# LED_Bar_Board.net
KiCad netlist of a schematic drawn in EAGLE
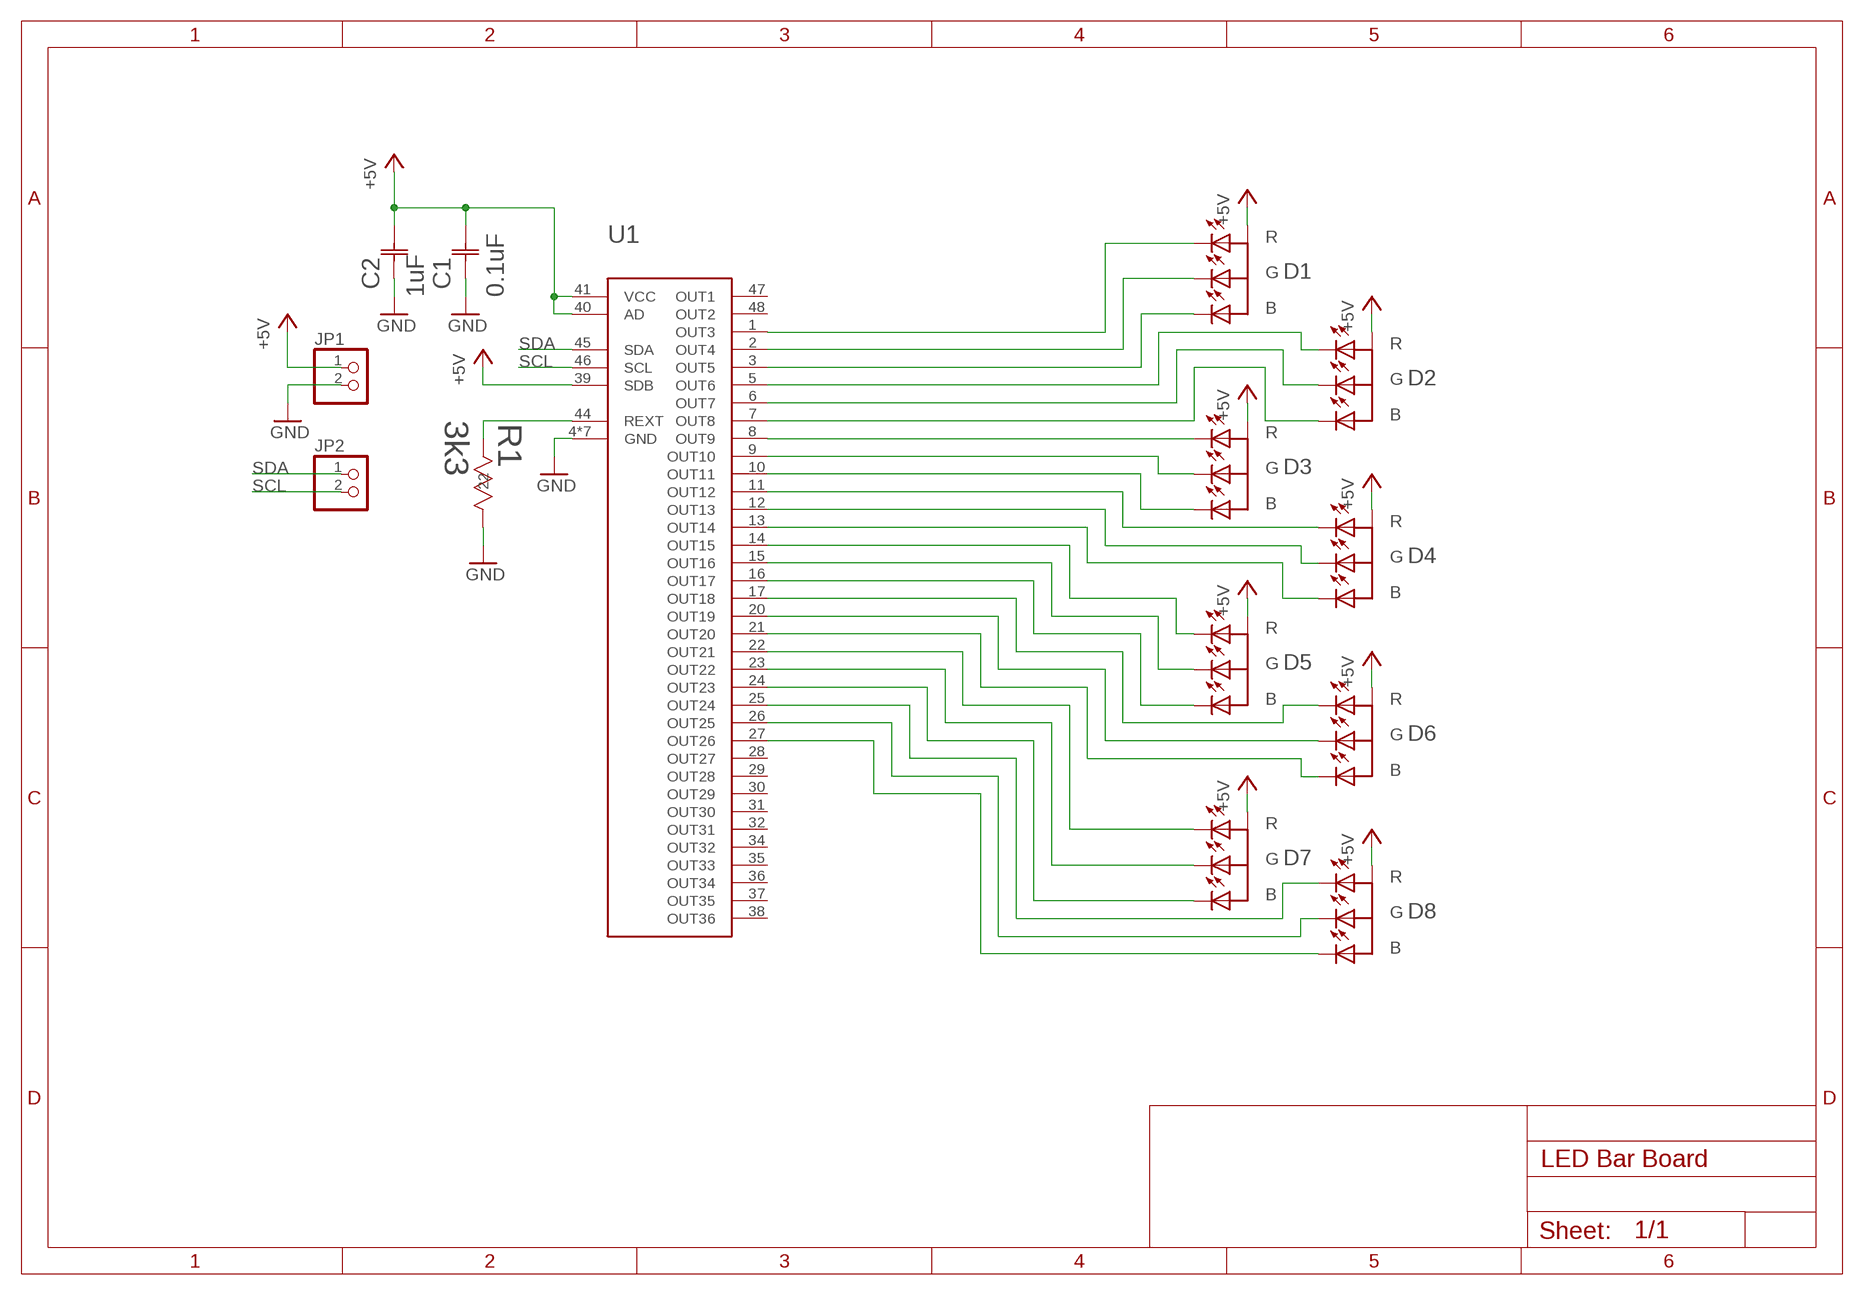
[diagram p0: schematic, sheet 1]

(export (version "E")
  (design (tool "Eeschema 10.0.6"))
  (components
    (comp (ref "C1")
      (value "0.1uF")
      (footprint "eagle-import:0805")
      (fields
        (field (name "MANUFACTURER_PART_NUMBER") "08055C104KAT2A")
        (field (name "COPYRIGHT") "Copyright C 2015 Accelerated Designs. All rights reserved")
      )
      (libsource (lib "eagle-import") (part "08055C104KAT2A"))
    )
    (comp (ref "C2")
      (value "1uF")
      (footprint "eagle-import:YAG_CC0805")
      (fields
        (field (name "MANUFACTURER_PART_NUMBER") "CC0805KKX7R7BB105")
        (field (name "COPYRIGHT") "Copyright C 2015 Accelerated Designs. All rights reserved")
      )
      (libsource (lib "eagle-import") (part "CC0805KKX7R7BB105"))
    )
    (comp (ref "D1")
      (value "ASMB-MTB0-0A3A2")
      (footprint "eagle-import:ASMB-MTB0_LED")
      (libsource (lib "eagle-import") (part "ASMB-MTB0-0A3A2"))
    )
    (comp (ref "D2")
      (value "ASMB-MTB0-0A3A2")
      (footprint "eagle-import:ASMB-MTB0_LED")
      (libsource (lib "eagle-import") (part "ASMB-MTB0-0A3A2"))
    )
    (comp (ref "D3")
      (value "ASMB-MTB0-0A3A2")
      (footprint "eagle-import:ASMB-MTB0_LED")
      (libsource (lib "eagle-import") (part "ASMB-MTB0-0A3A2"))
    )
    (comp (ref "D4")
      (value "ASMB-MTB0-0A3A2")
      (footprint "eagle-import:ASMB-MTB0_LED")
      (libsource (lib "eagle-import") (part "ASMB-MTB0-0A3A2"))
    )
    (comp (ref "D5")
      (value "ASMB-MTB0-0A3A2")
      (footprint "eagle-import:ASMB-MTB0_LED")
      (libsource (lib "eagle-import") (part "ASMB-MTB0-0A3A2"))
    )
    (comp (ref "D6")
      (value "ASMB-MTB0-0A3A2")
      (footprint "eagle-import:ASMB-MTB0_LED")
      (libsource (lib "eagle-import") (part "ASMB-MTB0-0A3A2"))
    )
    (comp (ref "D7")
      (value "ASMB-MTB0-0A3A2")
      (footprint "eagle-import:ASMB-MTB0_LED")
      (libsource (lib "eagle-import") (part "ASMB-MTB0-0A3A2"))
    )
    (comp (ref "D8")
      (value "ASMB-MTB0-0A3A2")
      (footprint "eagle-import:ASMB-MTB0_LED")
      (libsource (lib "eagle-import") (part "ASMB-MTB0-0A3A2"))
    )
    (comp (ref "JP1")
      (value "PINHD-1X2")
      (footprint "eagle-import:1X02")
      (libsource (lib "eagle-import") (part "PINHD-1X2"))
    )
    (comp (ref "JP2")
      (value "PINHD-1X2")
      (footprint "eagle-import:1X02")
      (libsource (lib "eagle-import") (part "PINHD-1X2"))
    )
    (comp (ref "R1")
      (value "3k3")
      (footprint "eagle-import:RC1206N-M")
      (fields (field (name "MANUFACTURER_PART_NUMBER") "RC1206JR073K3L"))
      (libsource (lib "eagle-import") (part "RC1206JR-073K3LRC1206N-M"))
    )
    (comp (ref "U1")
      (value "IS31FL3236")
      (footprint "eagle-import:TQFP-48")
      (libsource (lib "eagle-import") (part "IS31FL3236"))
    )
  )
  (nets
    (net (code "1") (name "+5V") (class "Default")
      (node (ref "C1") (pin "2") (pinfunction "2_2") (pintype "passive"))
      (node (ref "C2") (pin "2") (pinfunction "22_2") (pintype "passive"))
      (node (ref "D1") (pin "1") (pinfunction "A_1") (pintype "passive"))
      (node (ref "D2") (pin "1") (pinfunction "A_1") (pintype "passive"))
      (node (ref "D3") (pin "1") (pinfunction "A_1") (pintype "passive"))
      (node (ref "D4") (pin "1") (pinfunction "A_1") (pintype "passive"))
      (node (ref "D5") (pin "1") (pinfunction "A_1") (pintype "passive"))
      (node (ref "D6") (pin "1") (pinfunction "A_1") (pintype "passive"))
      (node (ref "D7") (pin "1") (pinfunction "A_1") (pintype "passive"))
      (node (ref "D8") (pin "1") (pinfunction "A_1") (pintype "passive"))
      (node (ref "JP1") (pin "1") (pinfunction "1_1") (pintype "passive"))
      (node (ref "U1") (pin "39") (pinfunction "SDB_39") (pintype "bidirectional"))
      (node (ref "U1") (pin "40") (pinfunction "AD_40") (pintype "bidirectional"))
      (node (ref "U1") (pin "41") (pinfunction "VCC_41") (pintype "bidirectional"))
    )
    (net (code "2") (name "/SCL") (class "Default")
      (node (ref "JP2") (pin "2") (pinfunction "2_2") (pintype "passive"))
      (node (ref "U1") (pin "46") (pinfunction "SCL_46") (pintype "bidirectional"))
    )
    (net (code "3") (name "/SDA") (class "Default")
      (node (ref "JP2") (pin "1") (pinfunction "1_1") (pintype "passive"))
      (node (ref "U1") (pin "45") (pinfunction "SDA_45") (pintype "bidirectional"))
    )
    (net (code "4") (name "GND") (class "Default")
      (node (ref "C1") (pin "1") (pinfunction "1_1") (pintype "passive"))
      (node (ref "C2") (pin "1") (pinfunction "11_1") (pintype "passive"))
      (node (ref "JP1") (pin "2") (pinfunction "2_2") (pintype "passive"))
      (node (ref "R1") (pin "1") (pinfunction "11_1") (pintype "passive"))
      (node (ref "U1") (pin "18") (pinfunction "GND_18") (pintype "bidirectional"))
      (node (ref "U1") (pin "19") (pinfunction "GND_19") (pintype "bidirectional"))
      (node (ref "U1") (pin "33") (pinfunction "GND_33") (pintype "bidirectional"))
      (node (ref "U1") (pin "4") (pinfunction "GND_4") (pintype "bidirectional"))
      (node (ref "U1") (pin "42") (pinfunction "GND_42") (pintype "bidirectional"))
      (node (ref "U1") (pin "43") (pinfunction "GND_43") (pintype "bidirectional"))
      (node (ref "U1") (pin "EP") (pinfunction "GND_EP") (pintype "bidirectional"))
    )
    (net (code "5") (name "Net-(D1-B)") (class "Default")
      (node (ref "D1") (pin "2") (pinfunction "B_2") (pintype "passive"))
      (node (ref "U1") (pin "3") (pinfunction "OUT5_3") (pintype "bidirectional"))
    )
    (net (code "6") (name "Net-(D1-G)") (class "Default")
      (node (ref "D1") (pin "3") (pinfunction "G_3") (pintype "passive"))
      (node (ref "U1") (pin "2") (pinfunction "OUT4_2") (pintype "bidirectional"))
    )
    (net (code "7") (name "Net-(D1-R)") (class "Default")
      (node (ref "D1") (pin "4") (pinfunction "R_4") (pintype "passive"))
      (node (ref "U1") (pin "1") (pinfunction "OUT3_1") (pintype "bidirectional"))
    )
    (net (code "8") (name "Net-(D2-B)") (class "Default")
      (node (ref "D2") (pin "2") (pinfunction "B_2") (pintype "passive"))
      (node (ref "U1") (pin "7") (pinfunction "OUT8_7") (pintype "bidirectional"))
    )
    (net (code "9") (name "Net-(D2-G)") (class "Default")
      (node (ref "D2") (pin "3") (pinfunction "G_3") (pintype "passive"))
      (node (ref "U1") (pin "6") (pinfunction "OUT7_6") (pintype "bidirectional"))
    )
    (net (code "10") (name "Net-(D2-R)") (class "Default")
      (node (ref "D2") (pin "4") (pinfunction "R_4") (pintype "passive"))
      (node (ref "U1") (pin "5") (pinfunction "OUT6_5") (pintype "bidirectional"))
    )
    (net (code "11") (name "Net-(D3-B)") (class "Default")
      (node (ref "D3") (pin "2") (pinfunction "B_2") (pintype "passive"))
      (node (ref "U1") (pin "10") (pinfunction "OUT11_10") (pintype "bidirectional"))
    )
    (net (code "12") (name "Net-(D3-G)") (class "Default")
      (node (ref "D3") (pin "3") (pinfunction "G_3") (pintype "passive"))
      (node (ref "U1") (pin "9") (pinfunction "OUT10_9") (pintype "bidirectional"))
    )
    (net (code "13") (name "Net-(D3-R)") (class "Default")
      (node (ref "D3") (pin "4") (pinfunction "R_4") (pintype "passive"))
      (node (ref "U1") (pin "8") (pinfunction "OUT9_8") (pintype "bidirectional"))
    )
    (net (code "14") (name "Net-(D4-B)") (class "Default")
      (node (ref "D4") (pin "2") (pinfunction "B_2") (pintype "passive"))
      (node (ref "U1") (pin "13") (pinfunction "OUT14_13") (pintype "bidirectional"))
    )
    (net (code "15") (name "Net-(D4-G)") (class "Default")
      (node (ref "D4") (pin "3") (pinfunction "G_3") (pintype "passive"))
      (node (ref "U1") (pin "12") (pinfunction "OUT13_12") (pintype "bidirectional"))
    )
    (net (code "16") (name "Net-(D4-R)") (class "Default")
      (node (ref "D4") (pin "4") (pinfunction "R_4") (pintype "passive"))
      (node (ref "U1") (pin "11") (pinfunction "OUT12_11") (pintype "bidirectional"))
    )
    (net (code "17") (name "Net-(D5-B)") (class "Default")
      (node (ref "D5") (pin "2") (pinfunction "B_2") (pintype "passive"))
      (node (ref "U1") (pin "16") (pinfunction "OUT17_16") (pintype "bidirectional"))
    )
    (net (code "18") (name "Net-(D5-G)") (class "Default")
      (node (ref "D5") (pin "3") (pinfunction "G_3") (pintype "passive"))
      (node (ref "U1") (pin "15") (pinfunction "OUT16_15") (pintype "bidirectional"))
    )
    (net (code "19") (name "Net-(D5-R)") (class "Default")
      (node (ref "D5") (pin "4") (pinfunction "R_4") (pintype "passive"))
      (node (ref "U1") (pin "14") (pinfunction "OUT15_14") (pintype "bidirectional"))
    )
    (net (code "20") (name "Net-(D6-B)") (class "Default")
      (node (ref "D6") (pin "2") (pinfunction "B_2") (pintype "passive"))
      (node (ref "U1") (pin "21") (pinfunction "OUT20_21") (pintype "bidirectional"))
    )
    (net (code "21") (name "Net-(D6-G)") (class "Default")
      (node (ref "D6") (pin "3") (pinfunction "G_3") (pintype "passive"))
      (node (ref "U1") (pin "20") (pinfunction "OUT19_20") (pintype "bidirectional"))
    )
    (net (code "22") (name "Net-(D6-R)") (class "Default")
      (node (ref "D6") (pin "4") (pinfunction "R_4") (pintype "passive"))
      (node (ref "U1") (pin "17") (pinfunction "OUT18_17") (pintype "bidirectional"))
    )
    (net (code "23") (name "Net-(D7-B)") (class "Default")
      (node (ref "D7") (pin "2") (pinfunction "B_2") (pintype "passive"))
      (node (ref "U1") (pin "24") (pinfunction "OUT23_24") (pintype "bidirectional"))
    )
    (net (code "24") (name "Net-(D7-G)") (class "Default")
      (node (ref "D7") (pin "3") (pinfunction "G_3") (pintype "passive"))
      (node (ref "U1") (pin "23") (pinfunction "OUT22_23") (pintype "bidirectional"))
    )
    (net (code "25") (name "Net-(D7-R)") (class "Default")
      (node (ref "D7") (pin "4") (pinfunction "R_4") (pintype "passive"))
      (node (ref "U1") (pin "22") (pinfunction "OUT21_22") (pintype "bidirectional"))
    )
    (net (code "26") (name "Net-(D8-B)") (class "Default")
      (node (ref "D8") (pin "2") (pinfunction "B_2") (pintype "passive"))
      (node (ref "U1") (pin "27") (pinfunction "OUT26_27") (pintype "bidirectional"))
    )
    (net (code "27") (name "Net-(D8-G)") (class "Default")
      (node (ref "D8") (pin "3") (pinfunction "G_3") (pintype "passive"))
      (node (ref "U1") (pin "26") (pinfunction "OUT25_26") (pintype "bidirectional"))
    )
    (net (code "28") (name "Net-(D8-R)") (class "Default")
      (node (ref "D8") (pin "4") (pinfunction "R_4") (pintype "passive"))
      (node (ref "U1") (pin "25") (pinfunction "OUT24_25") (pintype "bidirectional"))
    )
    (net (code "29") (name "Net-(R1-22)") (class "Default")
      (node (ref "R1") (pin "2") (pinfunction "22_2") (pintype "passive"))
      (node (ref "U1") (pin "44") (pinfunction "REXT_44") (pintype "bidirectional"))
    )
    (net (code "30") (name "unconnected-(U1-OUT1-Pad47)") (class "Default")
      (node (ref "U1") (pin "47") (pinfunction "OUT1_47") (pintype "bidirectional"))
    )
    (net (code "31") (name "unconnected-(U1-OUT2-Pad48)") (class "Default")
      (node (ref "U1") (pin "48") (pinfunction "OUT2_48") (pintype "bidirectional"))
    )
    (net (code "32") (name "unconnected-(U1-OUT27-Pad28)") (class "Default")
      (node (ref "U1") (pin "28") (pinfunction "OUT27_28") (pintype "bidirectional"))
    )
    (net (code "33") (name "unconnected-(U1-OUT28-Pad29)") (class "Default")
      (node (ref "U1") (pin "29") (pinfunction "OUT28_29") (pintype "bidirectional"))
    )
    (net (code "34") (name "unconnected-(U1-OUT29-Pad30)") (class "Default")
      (node (ref "U1") (pin "30") (pinfunction "OUT29_30") (pintype "bidirectional"))
    )
    (net (code "35") (name "unconnected-(U1-OUT30-Pad31)") (class "Default")
      (node (ref "U1") (pin "31") (pinfunction "OUT30_31") (pintype "bidirectional"))
    )
    (net (code "36") (name "unconnected-(U1-OUT31-Pad32)") (class "Default")
      (node (ref "U1") (pin "32") (pinfunction "OUT31_32") (pintype "bidirectional"))
    )
    (net (code "37") (name "unconnected-(U1-OUT32-Pad34)") (class "Default")
      (node (ref "U1") (pin "34") (pinfunction "OUT32_34") (pintype "bidirectional"))
    )
    (net (code "38") (name "unconnected-(U1-OUT33-Pad35)") (class "Default")
      (node (ref "U1") (pin "35") (pinfunction "OUT33_35") (pintype "bidirectional"))
    )
    (net (code "39") (name "unconnected-(U1-OUT34-Pad36)") (class "Default")
      (node (ref "U1") (pin "36") (pinfunction "OUT34_36") (pintype "bidirectional"))
    )
    (net (code "40") (name "unconnected-(U1-OUT35-Pad37)") (class "Default")
      (node (ref "U1") (pin "37") (pinfunction "OUT35_37") (pintype "bidirectional"))
    )
    (net (code "41") (name "unconnected-(U1-OUT36-Pad38)") (class "Default")
      (node (ref "U1") (pin "38") (pinfunction "OUT36_38") (pintype "bidirectional"))
    )
  )
)
